# Board_for_rover_motors_2021-02-24.net
KiCad netlist of a schematic drawn in EasyEDA
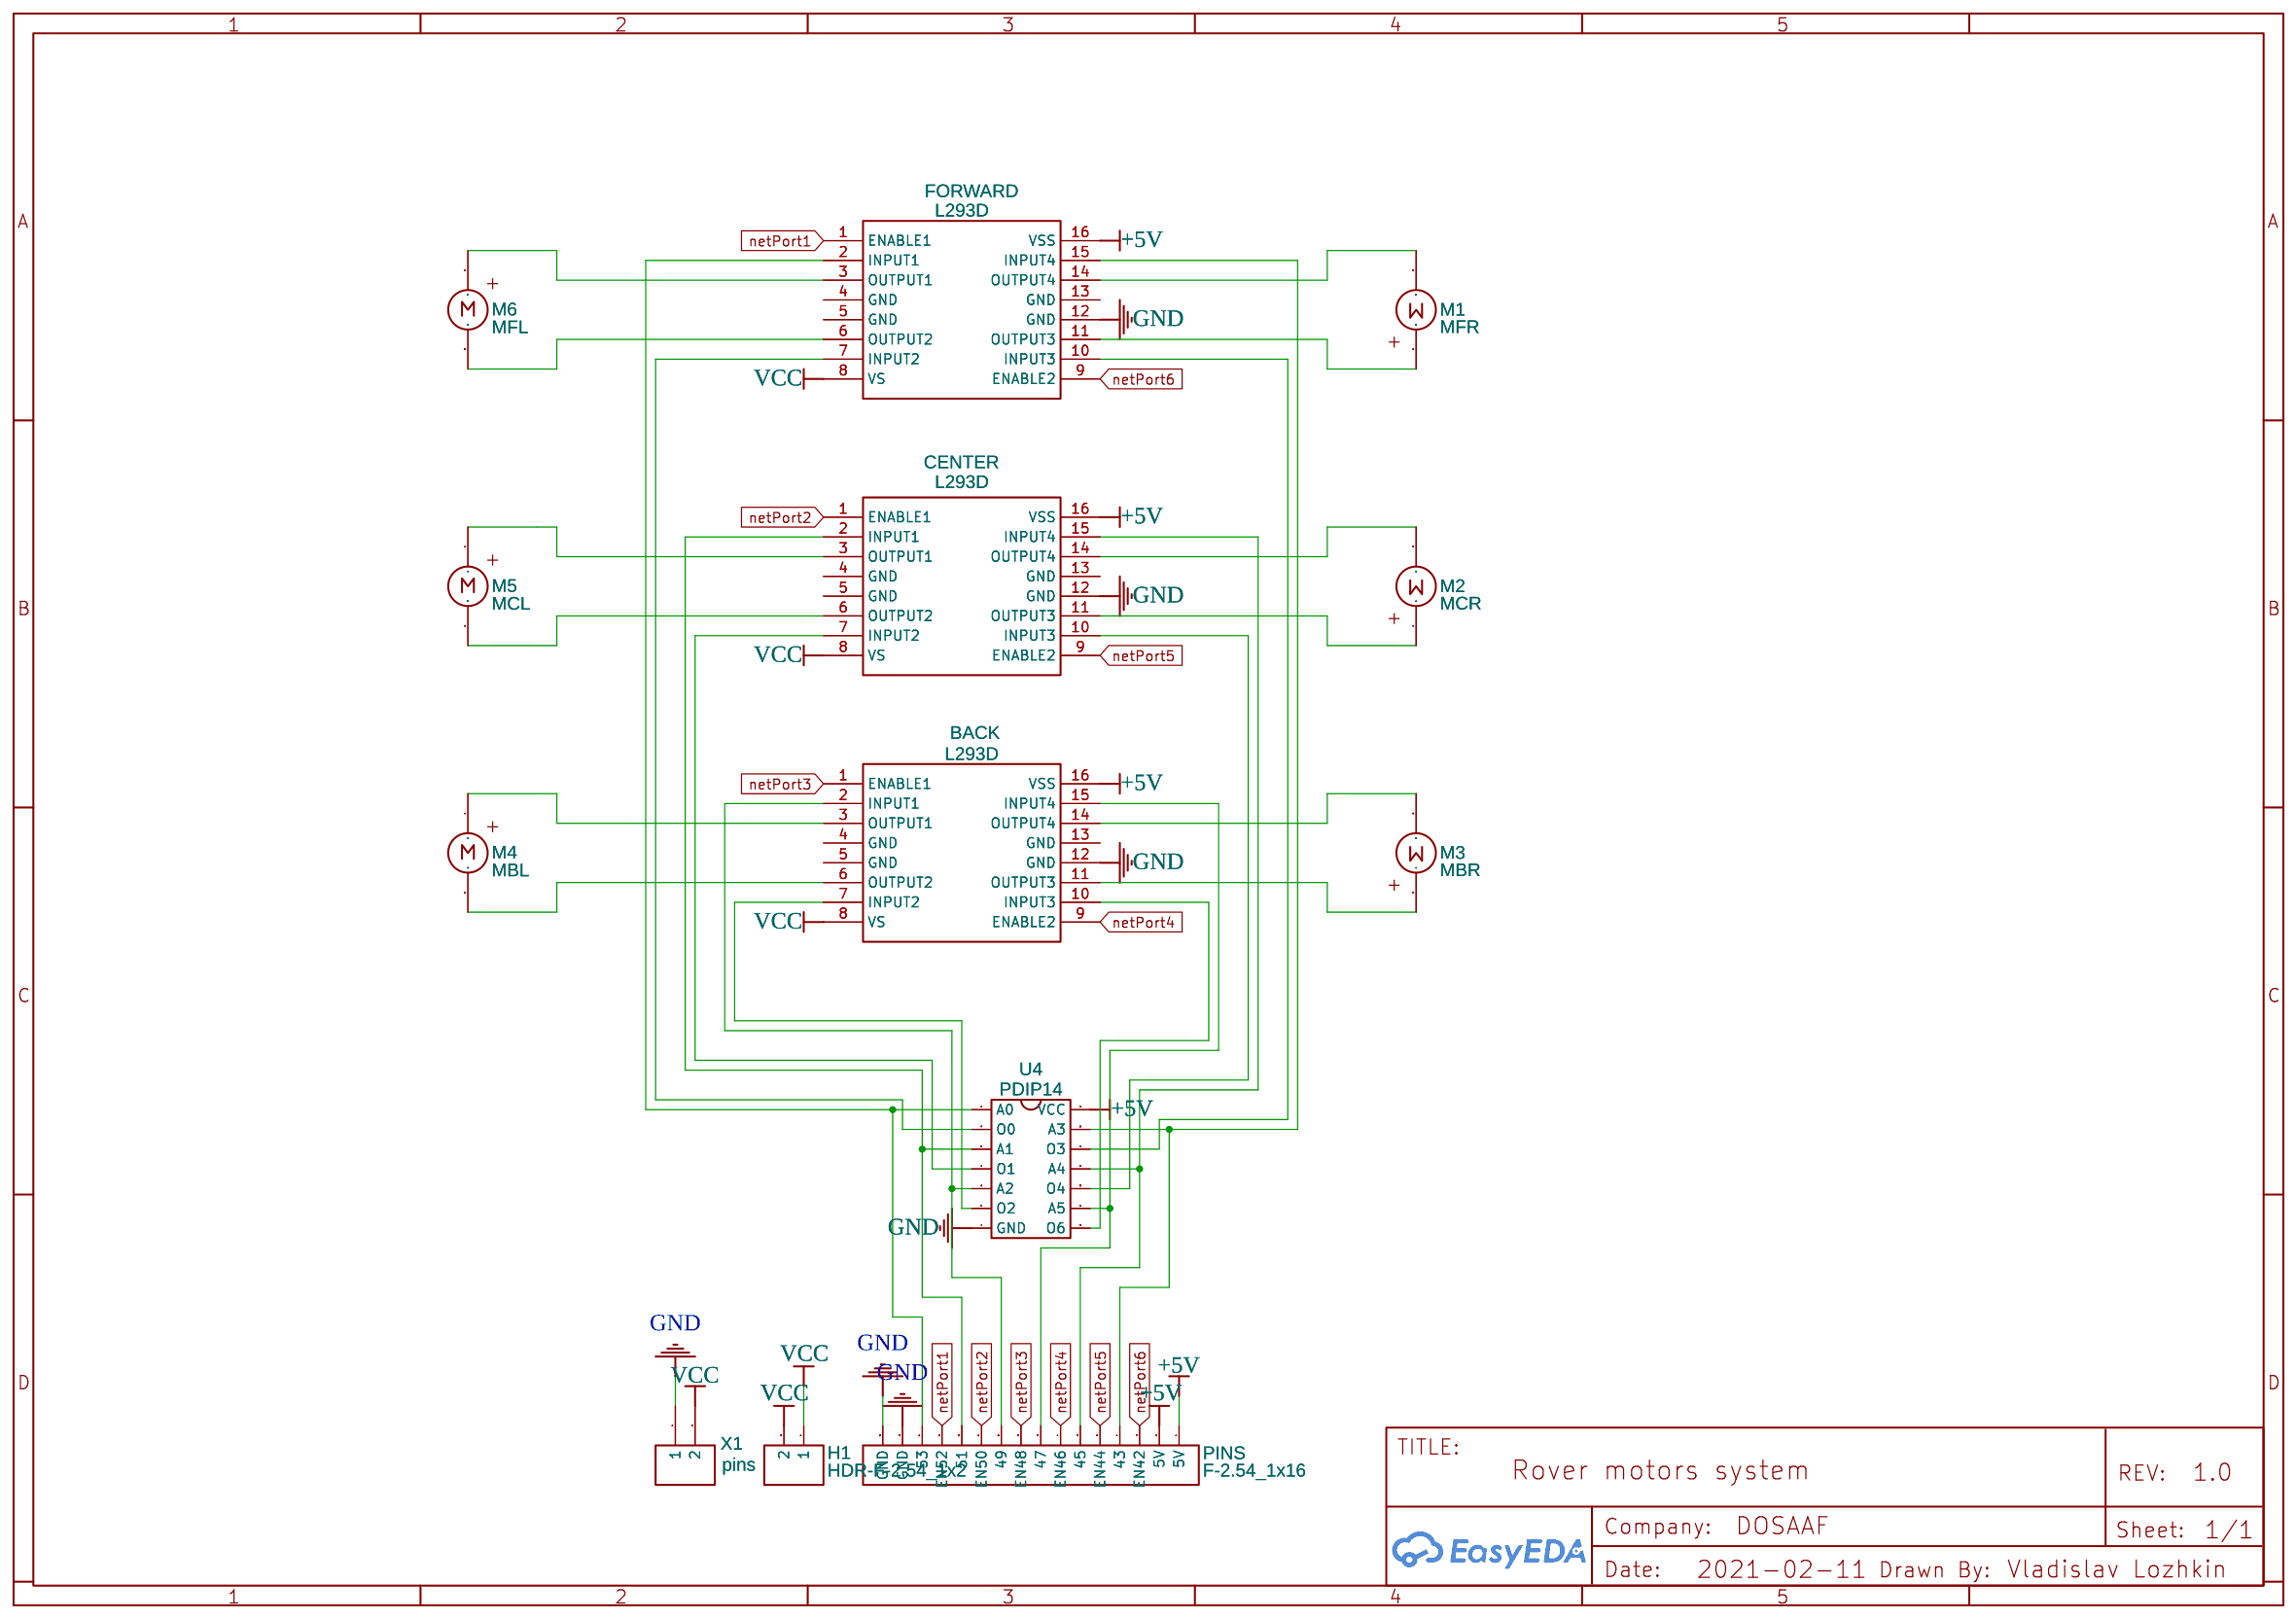
[diagram p0: schematic sheet]

(export (version "E")
  (design (tool "Eeschema 10.0.6"))
  (components
    (comp (ref "BACK")
      (value "L293D")
      (fields (field (name "BOM_Supplier Part") "C12340"))
      (libsource (lib "") (part "L293D_2"))
    )
    (comp (ref "CENTER")
      (value "L293D")
      (fields (field (name "BOM_Supplier Part") "C12340"))
      (libsource (lib "") (part "L293D_1"))
    )
    (comp (ref "FORWARD")
      (value "L293D")
      (fields (field (name "BOM_Supplier Part") "C12340"))
      (libsource (lib "") (part "L293D"))
    )
    (comp (ref "H1")
      (value "HDR-F-2.54_1x2")
      (fields (field (name "BOM_Supplier Part") "C49661"))
      (libsource (lib "") (part "HDR-F-2.54_1x2"))
    )
    (comp (ref "M1")
      (value "MFR")
      (fields (field (name "BOM_Manufacturer Part") "MOTOR"))
      (libsource (lib "") (part "MOTOR"))
    )
    (comp (ref "M2")
      (value "MCR")
      (fields (field (name "BOM_Manufacturer Part") "MOTOR"))
      (libsource (lib "") (part "MOTOR"))
    )
    (comp (ref "M3")
      (value "MBR")
      (fields (field (name "BOM_Manufacturer Part") "MOTOR"))
      (libsource (lib "") (part "MOTOR"))
    )
    (comp (ref "M4")
      (value "MBL")
      (fields (field (name "BOM_Manufacturer Part") "MOTOR"))
      (libsource (lib "") (part "MOTOR_1"))
    )
    (comp (ref "M5")
      (value "MCL")
      (fields (field (name "BOM_Manufacturer Part") "MOTOR"))
      (libsource (lib "") (part "MOTOR_1"))
    )
    (comp (ref "M6")
      (value "MFL")
      (fields (field (name "BOM_Manufacturer Part") "MOTOR"))
      (libsource (lib "") (part "MOTOR_1"))
    )
    (comp (ref "PINS")
      (value "F-2.54_1x16")
      (fields (field (name "BOM_Supplier Part") "C66987"))
      (libsource (lib "") (part "HDR-F-2.54_1x16"))
    )
    (comp (ref "U4") (value "PDIP14") (libsource (lib "") (part "PDIP14")))
    (comp (ref "X1") (value "pins") (libsource (lib "") (part "клеммник")))
  )
  (nets
    (net (code "1") (name "+5V") (class "Default")
      (node (ref "BACK") (pin "16") (pinfunction "VSS_16") (pintype "unspecified"))
      (node (ref "CENTER") (pin "16") (pinfunction "VSS_16") (pintype "unspecified"))
      (node (ref "FORWARD") (pin "16") (pinfunction "VSS_16") (pintype "unspecified"))
      (node (ref "PINS") (pin "1") (pinfunction "5V_1") (pintype "unspecified"))
      (node (ref "PINS") (pin "2") (pinfunction "5V_2") (pintype "unspecified"))
      (node (ref "U4") (pin "14") (pinfunction "VCC_14") (pintype "unspecified"))
    )
    (net (code "2") (name "GND") (class "Default")
      (node (ref "BACK") (pin "12") (pinfunction "GND_12") (pintype "unspecified"))
      (node (ref "CENTER") (pin "12") (pinfunction "GND_12") (pintype "unspecified"))
      (node (ref "FORWARD") (pin "12") (pinfunction "GND_12") (pintype "unspecified"))
      (node (ref "PINS") (pin "15") (pinfunction "GND_15") (pintype "unspecified"))
      (node (ref "PINS") (pin "16") (pinfunction "GND_16") (pintype "unspecified"))
      (node (ref "U4") (pin "7") (pinfunction "GND_7") (pintype "unspecified"))
      (node (ref "X1") (pin "1") (pinfunction "1_1") (pintype "unspecified"))
    )
    (net (code "3") (name "Net-(BACK-INPUT1)") (class "Default")
      (node (ref "BACK") (pin "2") (pinfunction "INPUT1_2") (pintype "unspecified"))
      (node (ref "PINS") (pin "10") (pinfunction "49_10") (pintype "unspecified"))
      (node (ref "U4") (pin "5") (pinfunction "A2_5") (pintype "unspecified"))
    )
    (net (code "4") (name "Net-(BACK-INPUT2)") (class "Default")
      (node (ref "BACK") (pin "7") (pinfunction "INPUT2_7") (pintype "unspecified"))
      (node (ref "U4") (pin "6") (pinfunction "O2_6") (pintype "unspecified"))
    )
    (net (code "5") (name "Net-(BACK-INPUT3)") (class "Default")
      (node (ref "BACK") (pin "10") (pinfunction "INPUT3_10") (pintype "unspecified"))
      (node (ref "U4") (pin "8") (pinfunction "O6_8") (pintype "unspecified"))
    )
    (net (code "6") (name "Net-(BACK-INPUT4)") (class "Default")
      (node (ref "BACK") (pin "15") (pinfunction "INPUT4_15") (pintype "unspecified"))
      (node (ref "PINS") (pin "8") (pinfunction "47_8") (pintype "unspecified"))
      (node (ref "U4") (pin "9") (pinfunction "A5_9") (pintype "unspecified"))
    )
    (net (code "7") (name "Net-(BACK-OUTPUT1)") (class "Default")
      (node (ref "BACK") (pin "3") (pinfunction "OUTPUT1_3") (pintype "unspecified"))
      (node (ref "M4") (pin "1") (pinfunction "1_1") (pintype "unspecified"))
    )
    (net (code "8") (name "Net-(BACK-OUTPUT2)") (class "Default")
      (node (ref "BACK") (pin "6") (pinfunction "OUTPUT2_6") (pintype "unspecified"))
      (node (ref "M4") (pin "2") (pinfunction "2_2") (pintype "unspecified"))
    )
    (net (code "9") (name "Net-(BACK-OUTPUT3)") (class "Default")
      (node (ref "BACK") (pin "11") (pinfunction "OUTPUT3_11") (pintype "unspecified"))
      (node (ref "M3") (pin "1") (pinfunction "1_1") (pintype "unspecified"))
    )
    (net (code "10") (name "Net-(BACK-OUTPUT4)") (class "Default")
      (node (ref "BACK") (pin "14") (pinfunction "OUTPUT4_14") (pintype "unspecified"))
      (node (ref "M3") (pin "2") (pinfunction "2_2") (pintype "unspecified"))
    )
    (net (code "11") (name "Net-(CENTER-INPUT1)") (class "Default")
      (node (ref "CENTER") (pin "2") (pinfunction "INPUT1_2") (pintype "unspecified"))
      (node (ref "PINS") (pin "12") (pinfunction "51_12") (pintype "unspecified"))
      (node (ref "U4") (pin "3") (pinfunction "A1_3") (pintype "unspecified"))
    )
    (net (code "12") (name "Net-(CENTER-INPUT2)") (class "Default")
      (node (ref "CENTER") (pin "7") (pinfunction "INPUT2_7") (pintype "unspecified"))
      (node (ref "U4") (pin "4") (pinfunction "O1_4") (pintype "unspecified"))
    )
    (net (code "13") (name "Net-(CENTER-INPUT3)") (class "Default")
      (node (ref "CENTER") (pin "10") (pinfunction "INPUT3_10") (pintype "unspecified"))
      (node (ref "U4") (pin "10") (pinfunction "O4_10") (pintype "unspecified"))
    )
    (net (code "14") (name "Net-(CENTER-INPUT4)") (class "Default")
      (node (ref "CENTER") (pin "15") (pinfunction "INPUT4_15") (pintype "unspecified"))
      (node (ref "PINS") (pin "6") (pinfunction "45_6") (pintype "unspecified"))
      (node (ref "U4") (pin "11") (pinfunction "A4_11") (pintype "unspecified"))
    )
    (net (code "15") (name "Net-(CENTER-OUTPUT1)") (class "Default")
      (node (ref "CENTER") (pin "3") (pinfunction "OUTPUT1_3") (pintype "unspecified"))
      (node (ref "M5") (pin "1") (pinfunction "1_1") (pintype "unspecified"))
    )
    (net (code "16") (name "Net-(CENTER-OUTPUT2)") (class "Default")
      (node (ref "CENTER") (pin "6") (pinfunction "OUTPUT2_6") (pintype "unspecified"))
      (node (ref "M5") (pin "2") (pinfunction "2_2") (pintype "unspecified"))
    )
    (net (code "17") (name "Net-(CENTER-OUTPUT3)") (class "Default")
      (node (ref "CENTER") (pin "11") (pinfunction "OUTPUT3_11") (pintype "unspecified"))
      (node (ref "M2") (pin "1") (pinfunction "1_1") (pintype "unspecified"))
    )
    (net (code "18") (name "Net-(CENTER-OUTPUT4)") (class "Default")
      (node (ref "CENTER") (pin "14") (pinfunction "OUTPUT4_14") (pintype "unspecified"))
      (node (ref "M2") (pin "2") (pinfunction "2_2") (pintype "unspecified"))
    )
    (net (code "19") (name "Net-(FORWARD-INPUT1)") (class "Default")
      (node (ref "FORWARD") (pin "2") (pinfunction "INPUT1_2") (pintype "unspecified"))
      (node (ref "PINS") (pin "14") (pinfunction "53_14") (pintype "unspecified"))
      (node (ref "U4") (pin "1") (pinfunction "A0_1") (pintype "unspecified"))
    )
    (net (code "20") (name "Net-(FORWARD-INPUT2)") (class "Default")
      (node (ref "FORWARD") (pin "7") (pinfunction "INPUT2_7") (pintype "unspecified"))
      (node (ref "U4") (pin "2") (pinfunction "O0_2") (pintype "unspecified"))
    )
    (net (code "21") (name "Net-(FORWARD-INPUT3)") (class "Default")
      (node (ref "FORWARD") (pin "10") (pinfunction "INPUT3_10") (pintype "unspecified"))
      (node (ref "U4") (pin "12") (pinfunction "O3_12") (pintype "unspecified"))
    )
    (net (code "22") (name "Net-(FORWARD-INPUT4)") (class "Default")
      (node (ref "FORWARD") (pin "15") (pinfunction "INPUT4_15") (pintype "unspecified"))
      (node (ref "PINS") (pin "4") (pinfunction "43_4") (pintype "unspecified"))
      (node (ref "U4") (pin "13") (pinfunction "A3_13") (pintype "unspecified"))
    )
    (net (code "23") (name "Net-(FORWARD-OUTPUT1)") (class "Default")
      (node (ref "FORWARD") (pin "3") (pinfunction "OUTPUT1_3") (pintype "unspecified"))
      (node (ref "M6") (pin "1") (pinfunction "1_1") (pintype "unspecified"))
    )
    (net (code "24") (name "Net-(FORWARD-OUTPUT2)") (class "Default")
      (node (ref "FORWARD") (pin "6") (pinfunction "OUTPUT2_6") (pintype "unspecified"))
      (node (ref "M6") (pin "2") (pinfunction "2_2") (pintype "unspecified"))
    )
    (net (code "25") (name "Net-(FORWARD-OUTPUT3)") (class "Default")
      (node (ref "FORWARD") (pin "11") (pinfunction "OUTPUT3_11") (pintype "unspecified"))
      (node (ref "M1") (pin "1") (pinfunction "1_1") (pintype "unspecified"))
    )
    (net (code "26") (name "Net-(FORWARD-OUTPUT4)") (class "Default")
      (node (ref "FORWARD") (pin "14") (pinfunction "OUTPUT4_14") (pintype "unspecified"))
      (node (ref "M1") (pin "2") (pinfunction "2_2") (pintype "unspecified"))
    )
    (net (code "27") (name "VCC") (class "Default")
      (node (ref "BACK") (pin "8") (pinfunction "VS_8") (pintype "unspecified"))
      (node (ref "CENTER") (pin "8") (pinfunction "VS_8") (pintype "unspecified"))
      (node (ref "FORWARD") (pin "8") (pinfunction "VS_8") (pintype "unspecified"))
      (node (ref "H1") (pin "1") (pinfunction "1_1") (pintype "input"))
      (node (ref "H1") (pin "2") (pinfunction "2_2") (pintype "input"))
      (node (ref "X1") (pin "2") (pinfunction "2_2") (pintype "unspecified"))
    )
    (net (code "28") (name "netPort1") (class "Default")
      (node (ref "FORWARD") (pin "1") (pinfunction "ENABLE1_1") (pintype "unspecified"))
      (node (ref "PINS") (pin "13") (pinfunction "EN52_13") (pintype "unspecified"))
    )
    (net (code "29") (name "netPort2") (class "Default")
      (node (ref "CENTER") (pin "1") (pinfunction "ENABLE1_1") (pintype "unspecified"))
      (node (ref "PINS") (pin "11") (pinfunction "EN50_11") (pintype "unspecified"))
    )
    (net (code "30") (name "netPort3") (class "Default")
      (node (ref "BACK") (pin "1") (pinfunction "ENABLE1_1") (pintype "unspecified"))
      (node (ref "PINS") (pin "9") (pinfunction "EN48_9") (pintype "unspecified"))
    )
    (net (code "31") (name "netPort4") (class "Default")
      (node (ref "BACK") (pin "9") (pinfunction "ENABLE2_9") (pintype "unspecified"))
      (node (ref "PINS") (pin "7") (pinfunction "EN46_7") (pintype "unspecified"))
    )
    (net (code "32") (name "netPort5") (class "Default")
      (node (ref "CENTER") (pin "9") (pinfunction "ENABLE2_9") (pintype "unspecified"))
      (node (ref "PINS") (pin "5") (pinfunction "EN44_5") (pintype "unspecified"))
    )
    (net (code "33") (name "netPort6") (class "Default")
      (node (ref "FORWARD") (pin "9") (pinfunction "ENABLE2_9") (pintype "unspecified"))
      (node (ref "PINS") (pin "3") (pinfunction "EN42_3") (pintype "unspecified"))
    )
    (net (code "34") (name "unconnected-(BACK-GND-Pad4)") (class "Default")
      (node (ref "BACK") (pin "4") (pinfunction "GND_4") (pintype "unspecified"))
    )
    (net (code "35") (name "unconnected-(BACK-GND-Pad5)") (class "Default")
      (node (ref "BACK") (pin "5") (pinfunction "GND_5") (pintype "unspecified"))
    )
    (net (code "36") (name "unconnected-(BACK-GND-Pad13)") (class "Default")
      (node (ref "BACK") (pin "13") (pinfunction "GND_13") (pintype "unspecified"))
    )
    (net (code "37") (name "unconnected-(CENTER-GND-Pad4)") (class "Default")
      (node (ref "CENTER") (pin "4") (pinfunction "GND_4") (pintype "unspecified"))
    )
    (net (code "38") (name "unconnected-(CENTER-GND-Pad5)") (class "Default")
      (node (ref "CENTER") (pin "5") (pinfunction "GND_5") (pintype "unspecified"))
    )
    (net (code "39") (name "unconnected-(CENTER-GND-Pad13)") (class "Default")
      (node (ref "CENTER") (pin "13") (pinfunction "GND_13") (pintype "unspecified"))
    )
    (net (code "40") (name "unconnected-(FORWARD-GND-Pad4)") (class "Default")
      (node (ref "FORWARD") (pin "4") (pinfunction "GND_4") (pintype "unspecified"))
    )
    (net (code "41") (name "unconnected-(FORWARD-GND-Pad5)") (class "Default")
      (node (ref "FORWARD") (pin "5") (pinfunction "GND_5") (pintype "unspecified"))
    )
    (net (code "42") (name "unconnected-(FORWARD-GND-Pad13)") (class "Default")
      (node (ref "FORWARD") (pin "13") (pinfunction "GND_13") (pintype "unspecified"))
    )
  )
)
